# MAPE-CUN-Large-022.net
KiCad netlist of a schematic drawn in EAGLE
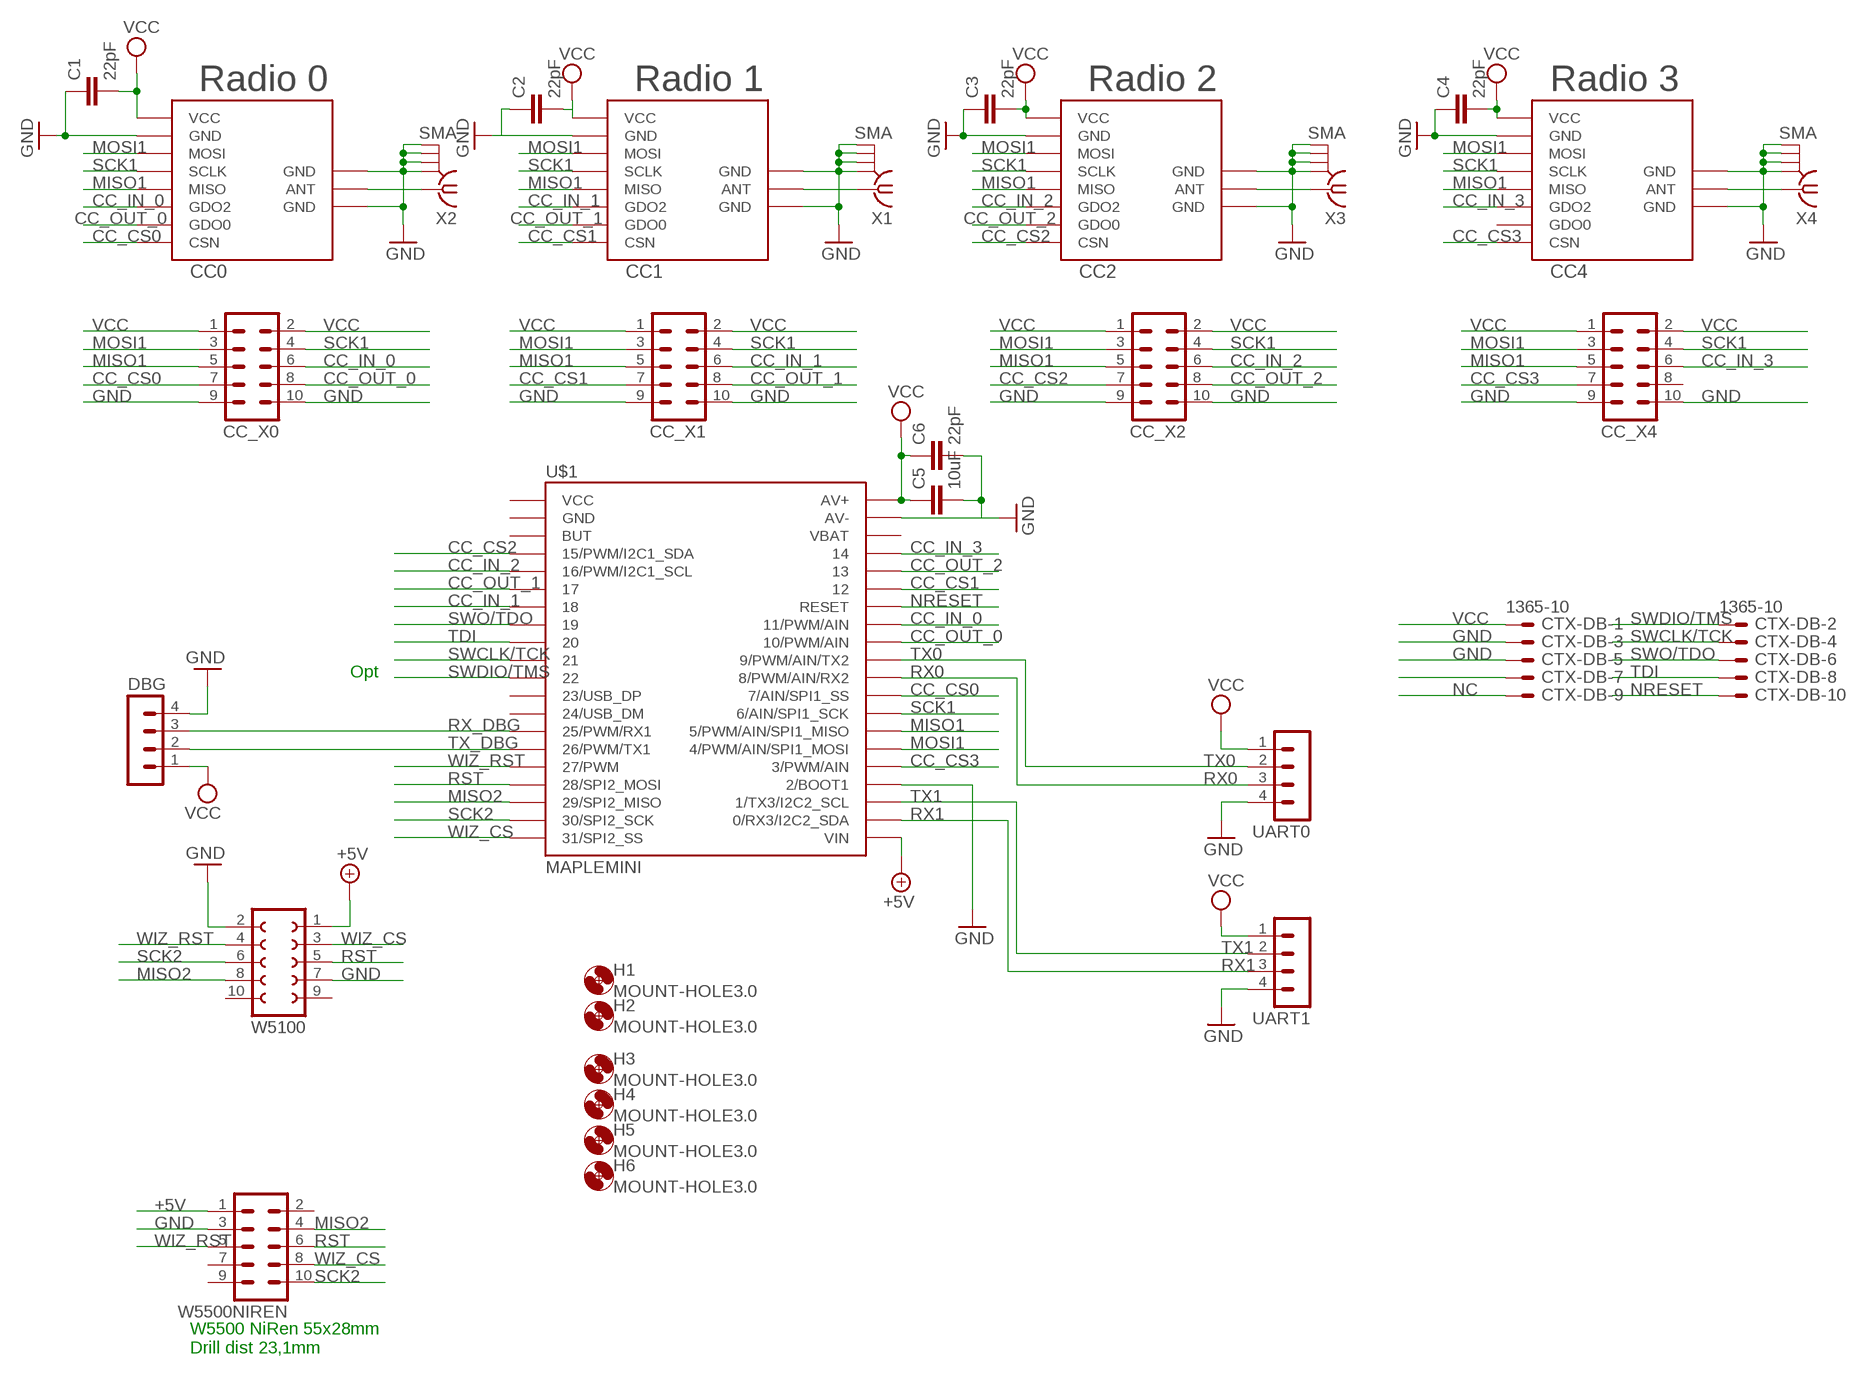
[diagram p0: schematic, sheet 1]

(export (version "E")
  (design (tool "Eeschema 10.0.6"))
  (components
    (comp (ref "C1")
      (value "22pF")
      (footprint "eagle-import:C0805")
      (libsource (lib "eagle-import") (part "C-EUC0805"))
    )
    (comp (ref "C2")
      (value "22pF")
      (footprint "eagle-import:C0805")
      (libsource (lib "eagle-import") (part "C-EUC0805"))
    )
    (comp (ref "C3")
      (value "22pF")
      (footprint "eagle-import:C0805")
      (libsource (lib "eagle-import") (part "C-EUC0805"))
    )
    (comp (ref "C4")
      (value "22pF")
      (footprint "eagle-import:C0805")
      (libsource (lib "eagle-import") (part "C-EUC0805"))
    )
    (comp (ref "C5")
      (value "10uF")
      (footprint "eagle-import:C1210")
      (libsource (lib "eagle-import") (part "C-EUC1210"))
    )
    (comp (ref "C6")
      (value "22pF")
      (footprint "eagle-import:C0805")
      (libsource (lib "eagle-import") (part "C-EUC0805"))
    )
    (comp (ref "CC0")
      (value "CC1101_MODULE1SMD")
      (footprint "eagle-import:CC1101_MODULE1_SMD")
      (libsource (lib "eagle-import") (part "CC1101_MODULE1SMD"))
    )
    (comp (ref "CC1")
      (value "CC1101_MODULE1SMD")
      (footprint "eagle-import:CC1101_MODULE1_SMD")
      (libsource (lib "eagle-import") (part "CC1101_MODULE1SMD"))
    )
    (comp (ref "CC2")
      (value "CC1101_MODULE1SMD")
      (footprint "eagle-import:CC1101_MODULE1_SMD")
      (libsource (lib "eagle-import") (part "CC1101_MODULE1SMD"))
    )
    (comp (ref "CC4")
      (value "CC1101_MODULE1SMD")
      (footprint "eagle-import:CC1101_MODULE1_SMD")
      (libsource (lib "eagle-import") (part "CC1101_MODULE1SMD"))
    )
    (comp (ref "CC_X0")
      (value "MA05-2")
      (footprint "eagle-import:MA05-2")
      (libsource (lib "eagle-import") (part "MA05-2"))
    )
    (comp (ref "CC_X1")
      (value "MA05-2")
      (footprint "eagle-import:MA05-2")
      (libsource (lib "eagle-import") (part "MA05-2"))
    )
    (comp (ref "CC_X2")
      (value "MA05-2")
      (footprint "eagle-import:MA05-2")
      (libsource (lib "eagle-import") (part "MA05-2"))
    )
    (comp (ref "CC_X4")
      (value "MA05-2")
      (footprint "eagle-import:MA05-2")
      (libsource (lib "eagle-import") (part "MA05-2"))
    )
    (comp (ref "CTX-DB")
      (value "1365-10")
      (footprint "eagle-import:1365-10")
      (libsource (lib "eagle-import") (part "1365-10"))
    )
    (comp (ref "DBG")
      (value "MA04-1")
      (footprint "eagle-import:MA04-1")
      (libsource (lib "eagle-import") (part "MA04-1"))
    )
    (comp (ref "H1")
      (value "MOUNT-HOLE3.0")
      (footprint "eagle-import:3,0")
      (libsource (lib "eagle-import") (part "MOUNT-HOLE3.0"))
    )
    (comp (ref "H2")
      (value "MOUNT-HOLE3.0")
      (footprint "eagle-import:3,0")
      (libsource (lib "eagle-import") (part "MOUNT-HOLE3.0"))
    )
    (comp (ref "H3")
      (value "MOUNT-HOLE3.0")
      (footprint "eagle-import:3,0")
      (libsource (lib "eagle-import") (part "MOUNT-HOLE3.0"))
    )
    (comp (ref "H4")
      (value "MOUNT-HOLE3.0")
      (footprint "eagle-import:3,0")
      (libsource (lib "eagle-import") (part "MOUNT-HOLE3.0"))
    )
    (comp (ref "H5")
      (value "MOUNT-HOLE3.0")
      (footprint "eagle-import:3,0")
      (libsource (lib "eagle-import") (part "MOUNT-HOLE3.0"))
    )
    (comp (ref "H6")
      (value "MOUNT-HOLE3.0")
      (footprint "eagle-import:3,0")
      (libsource (lib "eagle-import") (part "MOUNT-HOLE3.0"))
    )
    (comp (ref "U$1")
      (value "MAPLEMINI")
      (footprint "eagle-import:20-DIP")
      (libsource (lib "eagle-import") (part "MAPLEMINI"))
    )
    (comp (ref "UART0")
      (value "MA04-1")
      (footprint "eagle-import:MA04-1")
      (libsource (lib "eagle-import") (part "MA04-1"))
    )
    (comp (ref "UART1")
      (value "MA04-1")
      (footprint "eagle-import:MA04-1")
      (libsource (lib "eagle-import") (part "MA04-1"))
    )
    (comp (ref "W5100")
      (value "FE05-2")
      (footprint "eagle-import:FE05-2")
      (libsource (lib "eagle-import") (part "FE05-2"))
    )
    (comp (ref "W5500NIREN")
      (value "MA05-2")
      (footprint "eagle-import:MA05-2")
      (libsource (lib "eagle-import") (part "MA05-2"))
    )
    (comp (ref "X1")
      (value "SMA")
      (footprint "eagle-import:SMA")
      (libsource (lib "eagle-import") (part "SMA"))
    )
    (comp (ref "X2")
      (value "SMA")
      (footprint "eagle-import:SMA")
      (libsource (lib "eagle-import") (part "SMA"))
    )
    (comp (ref "X3")
      (value "SMA")
      (footprint "eagle-import:SMA")
      (libsource (lib "eagle-import") (part "SMA"))
    )
    (comp (ref "X4")
      (value "SMA")
      (footprint "eagle-import:SMA")
      (libsource (lib "eagle-import") (part "SMA"))
    )
  )
  (nets
    (net (code "1") (name "+5V") (class "Default")
      (node (ref "U$1") (pin "21") (pinfunction "VIN_21") (pintype "bidirectional"))
      (node (ref "W5100") (pin "1") (pinfunction "1_1") (pintype "passive"))
      (node (ref "W5500NIREN") (pin "1") (pinfunction "1_1") (pintype "passive"))
    )
    (net (code "2") (name "/CC_CS0") (class "Default")
      (node (ref "CC0") (pin "CSN") (pinfunction "CSN_CSN") (pintype "bidirectional"))
      (node (ref "CC_X0") (pin "7") (pinfunction "7_7") (pintype "passive"))
      (node (ref "U$1") (pin "29") (pinfunction "7/AIN/SPI1_SS_29") (pintype "bidirectional"))
    )
    (net (code "3") (name "/CC_CS1") (class "Default")
      (node (ref "CC1") (pin "CSN") (pinfunction "CSN_CSN") (pintype "bidirectional"))
      (node (ref "CC_X1") (pin "7") (pinfunction "7_7") (pintype "passive"))
      (node (ref "U$1") (pin "35") (pinfunction "12_35") (pintype "bidirectional"))
    )
    (net (code "4") (name "/CC_CS2") (class "Default")
      (node (ref "CC2") (pin "CSN") (pinfunction "CSN_CSN") (pintype "bidirectional"))
      (node (ref "CC_X2") (pin "7") (pinfunction "7_7") (pintype "passive"))
      (node (ref "U$1") (pin "4") (pinfunction "15/PWM/I2C1_SDA_4") (pintype "bidirectional"))
    )
    (net (code "5") (name "/CC_CS3") (class "Default")
      (node (ref "CC4") (pin "CSN") (pinfunction "CSN_CSN") (pintype "bidirectional"))
      (node (ref "CC_X4") (pin "7") (pinfunction "7_7") (pintype "passive"))
      (node (ref "U$1") (pin "25") (pinfunction "3/PWM/AIN_25") (pintype "bidirectional"))
    )
    (net (code "6") (name "/CC_IN_0") (class "Default")
      (node (ref "CC0") (pin "GDO2") (pinfunction "GDO2_GDO2") (pintype "bidirectional"))
      (node (ref "CC_X0") (pin "6") (pinfunction "6_6") (pintype "passive"))
      (node (ref "U$1") (pin "33") (pinfunction "11/PWM/AIN_33") (pintype "bidirectional"))
    )
    (net (code "7") (name "/CC_IN_1") (class "Default")
      (node (ref "CC1") (pin "GDO2") (pinfunction "GDO2_GDO2") (pintype "bidirectional"))
      (node (ref "CC_X1") (pin "6") (pinfunction "6_6") (pintype "passive"))
      (node (ref "U$1") (pin "7") (pinfunction "18_7") (pintype "bidirectional"))
    )
    (net (code "8") (name "/CC_IN_2") (class "Default")
      (node (ref "CC2") (pin "GDO2") (pinfunction "GDO2_GDO2") (pintype "bidirectional"))
      (node (ref "CC_X2") (pin "6") (pinfunction "6_6") (pintype "passive"))
      (node (ref "U$1") (pin "5") (pinfunction "16/PWM/I2C1_SCL_5") (pintype "bidirectional"))
    )
    (net (code "9") (name "/CC_IN_3") (class "Default")
      (node (ref "CC4") (pin "GDO2") (pinfunction "GDO2_GDO2") (pintype "bidirectional"))
      (node (ref "CC_X4") (pin "6") (pinfunction "6_6") (pintype "passive"))
      (node (ref "U$1") (pin "37") (pinfunction "14_37") (pintype "bidirectional"))
    )
    (net (code "10") (name "/CC_OUT_0") (class "Default")
      (node (ref "CC0") (pin "GDO0") (pinfunction "GDO0_GDO0") (pintype "bidirectional"))
      (node (ref "CC_X0") (pin "8") (pinfunction "8_8") (pintype "passive"))
      (node (ref "U$1") (pin "32") (pinfunction "10/PWM/AIN_32") (pintype "bidirectional"))
    )
    (net (code "11") (name "/CC_OUT_1") (class "Default")
      (node (ref "CC1") (pin "GDO0") (pinfunction "GDO0_GDO0") (pintype "bidirectional"))
      (node (ref "CC_X1") (pin "8") (pinfunction "8_8") (pintype "passive"))
      (node (ref "U$1") (pin "6") (pinfunction "17_6") (pintype "bidirectional"))
    )
    (net (code "12") (name "/CC_OUT_2") (class "Default")
      (node (ref "CC2") (pin "GDO0") (pinfunction "GDO0_GDO0") (pintype "bidirectional"))
      (node (ref "CC_X2") (pin "8") (pinfunction "8_8") (pintype "passive"))
      (node (ref "U$1") (pin "36") (pinfunction "13_36") (pintype "bidirectional"))
    )
    (net (code "13") (name "/MISO1") (class "Default")
      (node (ref "CC0") (pin "MISO") (pinfunction "MISO_MISO") (pintype "bidirectional"))
      (node (ref "CC1") (pin "MISO") (pinfunction "MISO_MISO") (pintype "bidirectional"))
      (node (ref "CC2") (pin "MISO") (pinfunction "MISO_MISO") (pintype "bidirectional"))
      (node (ref "CC4") (pin "MISO") (pinfunction "MISO_MISO") (pintype "bidirectional"))
      (node (ref "CC_X0") (pin "5") (pinfunction "5_5") (pintype "passive"))
      (node (ref "CC_X1") (pin "5") (pinfunction "5_5") (pintype "passive"))
      (node (ref "CC_X2") (pin "5") (pinfunction "5_5") (pintype "passive"))
      (node (ref "CC_X4") (pin "5") (pinfunction "5_5") (pintype "passive"))
      (node (ref "U$1") (pin "27") (pinfunction "5/PWM/AIN/SPI1_MISO_27") (pintype "bidirectional"))
    )
    (net (code "14") (name "/MISO2") (class "Default")
      (node (ref "U$1") (pin "18") (pinfunction "29/SPI2_MISO_18") (pintype "bidirectional"))
      (node (ref "W5100") (pin "8") (pinfunction "8_8") (pintype "passive"))
      (node (ref "W5500NIREN") (pin "4") (pinfunction "4_4") (pintype "passive"))
    )
    (net (code "15") (name "/MOSI1") (class "Default")
      (node (ref "CC0") (pin "MOSI") (pinfunction "MOSI_MOSI") (pintype "bidirectional"))
      (node (ref "CC1") (pin "MOSI") (pinfunction "MOSI_MOSI") (pintype "bidirectional"))
      (node (ref "CC2") (pin "MOSI") (pinfunction "MOSI_MOSI") (pintype "bidirectional"))
      (node (ref "CC4") (pin "MOSI") (pinfunction "MOSI_MOSI") (pintype "bidirectional"))
      (node (ref "CC_X0") (pin "3") (pinfunction "3_3") (pintype "passive"))
      (node (ref "CC_X1") (pin "3") (pinfunction "3_3") (pintype "passive"))
      (node (ref "CC_X2") (pin "3") (pinfunction "3_3") (pintype "passive"))
      (node (ref "CC_X4") (pin "3") (pinfunction "3_3") (pintype "passive"))
      (node (ref "U$1") (pin "26") (pinfunction "4/PWM/AIN/SPI1_MOSI_26") (pintype "bidirectional"))
    )
    (net (code "16") (name "/NC") (class "Default")
      (node (ref "CTX-DB") (pin "9") (pinfunction "S_9") (pintype "passive"))
    )
    (net (code "17") (name "/NRESET") (class "Default")
      (node (ref "CTX-DB") (pin "10") (pinfunction "S_10") (pintype "passive"))
      (node (ref "U$1") (pin "34") (pinfunction "RESET_34") (pintype "bidirectional"))
    )
    (net (code "18") (name "/RST") (class "Default")
      (node (ref "U$1") (pin "17") (pinfunction "28/SPI2_MOSI_17") (pintype "bidirectional"))
      (node (ref "W5100") (pin "5") (pinfunction "5_5") (pintype "passive"))
      (node (ref "W5500NIREN") (pin "6") (pinfunction "6_6") (pintype "passive"))
    )
    (net (code "19") (name "/RX0") (class "Default")
      (node (ref "U$1") (pin "30") (pinfunction "8/PWM/AIN/RX2_30") (pintype "bidirectional"))
      (node (ref "UART0") (pin "3") (pinfunction "3_3") (pintype "passive"))
    )
    (net (code "20") (name "/RX1") (class "Default")
      (node (ref "U$1") (pin "22") (pinfunction "0/RX3/I2C2_SDA_22") (pintype "bidirectional"))
      (node (ref "UART1") (pin "3") (pinfunction "3_3") (pintype "passive"))
    )
    (net (code "21") (name "/RX_DBG") (class "Default")
      (node (ref "DBG") (pin "3") (pinfunction "3_3") (pintype "passive"))
      (node (ref "U$1") (pin "14") (pinfunction "25/PWM/RX1_14") (pintype "bidirectional"))
    )
    (net (code "22") (name "/SCK1") (class "Default")
      (node (ref "CC0") (pin "SCLK") (pinfunction "SCLK_SCLK") (pintype "bidirectional"))
      (node (ref "CC1") (pin "SCLK") (pinfunction "SCLK_SCLK") (pintype "bidirectional"))
      (node (ref "CC2") (pin "SCLK") (pinfunction "SCLK_SCLK") (pintype "bidirectional"))
      (node (ref "CC4") (pin "SCLK") (pinfunction "SCLK_SCLK") (pintype "bidirectional"))
      (node (ref "CC_X0") (pin "4") (pinfunction "4_4") (pintype "passive"))
      (node (ref "CC_X1") (pin "4") (pinfunction "4_4") (pintype "passive"))
      (node (ref "CC_X2") (pin "4") (pinfunction "4_4") (pintype "passive"))
      (node (ref "CC_X4") (pin "4") (pinfunction "4_4") (pintype "passive"))
      (node (ref "U$1") (pin "28") (pinfunction "6/AIN/SPI1_SCK_28") (pintype "bidirectional"))
    )
    (net (code "23") (name "/SCK2") (class "Default")
      (node (ref "U$1") (pin "19") (pinfunction "30/SPI2_SCK_19") (pintype "bidirectional"))
      (node (ref "W5100") (pin "6") (pinfunction "6_6") (pintype "passive"))
      (node (ref "W5500NIREN") (pin "10") (pinfunction "10_10") (pintype "passive"))
    )
    (net (code "24") (name "/SWCLK{slash}TCK") (class "Default")
      (node (ref "CTX-DB") (pin "4") (pinfunction "S_4") (pintype "passive"))
      (node (ref "U$1") (pin "10") (pinfunction "21_10") (pintype "bidirectional"))
    )
    (net (code "25") (name "/SWDIO{slash}TMS") (class "Default")
      (node (ref "CTX-DB") (pin "2") (pinfunction "S_2") (pintype "passive"))
      (node (ref "U$1") (pin "11") (pinfunction "22_11") (pintype "bidirectional"))
    )
    (net (code "26") (name "/SWO{slash}TDO") (class "Default")
      (node (ref "CTX-DB") (pin "6") (pinfunction "S_6") (pintype "passive"))
      (node (ref "U$1") (pin "8") (pinfunction "19_8") (pintype "bidirectional"))
    )
    (net (code "27") (name "/TDI") (class "Default")
      (node (ref "CTX-DB") (pin "8") (pinfunction "S_8") (pintype "passive"))
      (node (ref "U$1") (pin "9") (pinfunction "20_9") (pintype "bidirectional"))
    )
    (net (code "28") (name "/TX0") (class "Default")
      (node (ref "U$1") (pin "31") (pinfunction "9/PWM/AIN/TX2_31") (pintype "bidirectional"))
      (node (ref "UART0") (pin "2") (pinfunction "2_2") (pintype "passive"))
    )
    (net (code "29") (name "/TX1") (class "Default")
      (node (ref "U$1") (pin "23") (pinfunction "1/TX3/I2C2_SCL_23") (pintype "bidirectional"))
      (node (ref "UART1") (pin "2") (pinfunction "2_2") (pintype "passive"))
    )
    (net (code "30") (name "/TX_DBG") (class "Default")
      (node (ref "DBG") (pin "2") (pinfunction "2_2") (pintype "passive"))
      (node (ref "U$1") (pin "15") (pinfunction "26/PWM/TX1_15") (pintype "bidirectional"))
    )
    (net (code "31") (name "/WIZ_CS") (class "Default")
      (node (ref "U$1") (pin "20") (pinfunction "31/SPI2_SS_20") (pintype "bidirectional"))
      (node (ref "W5100") (pin "3") (pinfunction "3_3") (pintype "passive"))
      (node (ref "W5500NIREN") (pin "8") (pinfunction "8_8") (pintype "passive"))
    )
    (net (code "32") (name "/WIZ_RST") (class "Default")
      (node (ref "U$1") (pin "16") (pinfunction "27/PWM_16") (pintype "bidirectional"))
      (node (ref "W5100") (pin "4") (pinfunction "4_4") (pintype "passive"))
      (node (ref "W5500NIREN") (pin "5") (pinfunction "5_5") (pintype "passive"))
    )
    (net (code "33") (name "GND") (class "Default")
      (node (ref "C1") (pin "1") (pinfunction "1_1") (pintype "passive"))
      (node (ref "C2") (pin "1") (pinfunction "1_1") (pintype "passive"))
      (node (ref "C3") (pin "1") (pinfunction "1_1") (pintype "passive"))
      (node (ref "C4") (pin "1") (pinfunction "1_1") (pintype "passive"))
      (node (ref "C5") (pin "2") (pinfunction "2_2") (pintype "passive"))
      (node (ref "C6") (pin "2") (pinfunction "2_2") (pintype "passive"))
      (node (ref "CC0") (pin "GND@0") (pinfunction "GND_GND@0") (pintype "power_in"))
      (node (ref "CC0") (pin "GND@1") (pinfunction "GND_GND@1") (pintype "power_in"))
      (node (ref "CC0") (pin "GND@2") (pinfunction "GND_GND@2") (pintype "power_in"))
      (node (ref "CC1") (pin "GND@0") (pinfunction "GND_GND@0") (pintype "power_in"))
      (node (ref "CC1") (pin "GND@1") (pinfunction "GND_GND@1") (pintype "power_in"))
      (node (ref "CC1") (pin "GND@2") (pinfunction "GND_GND@2") (pintype "power_in"))
      (node (ref "CC2") (pin "GND@0") (pinfunction "GND_GND@0") (pintype "power_in"))
      (node (ref "CC2") (pin "GND@1") (pinfunction "GND_GND@1") (pintype "power_in"))
      (node (ref "CC2") (pin "GND@2") (pinfunction "GND_GND@2") (pintype "power_in"))
      (node (ref "CC4") (pin "GND@0") (pinfunction "GND_GND@0") (pintype "power_in"))
      (node (ref "CC4") (pin "GND@1") (pinfunction "GND_GND@1") (pintype "power_in"))
      (node (ref "CC4") (pin "GND@2") (pinfunction "GND_GND@2") (pintype "power_in"))
      (node (ref "CC_X0") (pin "10") (pinfunction "10_10") (pintype "passive"))
      (node (ref "CC_X0") (pin "9") (pinfunction "9_9") (pintype "passive"))
      (node (ref "CC_X1") (pin "10") (pinfunction "10_10") (pintype "passive"))
      (node (ref "CC_X1") (pin "9") (pinfunction "9_9") (pintype "passive"))
      (node (ref "CC_X2") (pin "10") (pinfunction "10_10") (pintype "passive"))
      (node (ref "CC_X2") (pin "9") (pinfunction "9_9") (pintype "passive"))
      (node (ref "CC_X4") (pin "10") (pinfunction "10_10") (pintype "passive"))
      (node (ref "CC_X4") (pin "9") (pinfunction "9_9") (pintype "passive"))
      (node (ref "CTX-DB") (pin "3") (pinfunction "S_3") (pintype "passive"))
      (node (ref "CTX-DB") (pin "5") (pinfunction "S_5") (pintype "passive"))
      (node (ref "DBG") (pin "4") (pinfunction "4_4") (pintype "passive"))
      (node (ref "U$1") (pin "24") (pinfunction "2/BOOT1_24") (pintype "bidirectional"))
      (node (ref "U$1") (pin "39") (pinfunction "AV-_39") (pintype "bidirectional"))
      (node (ref "UART0") (pin "4") (pinfunction "4_4") (pintype "passive"))
      (node (ref "UART1") (pin "4") (pinfunction "4_4") (pintype "passive"))
      (node (ref "W5100") (pin "2") (pinfunction "2_2") (pintype "passive"))
      (node (ref "W5100") (pin "7") (pinfunction "7_7") (pintype "passive"))
      (node (ref "W5500NIREN") (pin "3") (pinfunction "3_3") (pintype "passive"))
      (node (ref "X1") (pin "GND@1") (pinfunction "2_GND@1") (pintype "passive"))
      (node (ref "X1") (pin "GND@2") (pinfunction "3_GND@2") (pintype "passive"))
      (node (ref "X1") (pin "GND@3") (pinfunction "4_GND@3") (pintype "passive"))
      (node (ref "X1") (pin "GND@4") (pinfunction "5_GND@4") (pintype "passive"))
      (node (ref "X2") (pin "GND@1") (pinfunction "2_GND@1") (pintype "passive"))
      (node (ref "X2") (pin "GND@2") (pinfunction "3_GND@2") (pintype "passive"))
      (node (ref "X2") (pin "GND@3") (pinfunction "4_GND@3") (pintype "passive"))
      (node (ref "X2") (pin "GND@4") (pinfunction "5_GND@4") (pintype "passive"))
      (node (ref "X3") (pin "GND@1") (pinfunction "2_GND@1") (pintype "passive"))
      (node (ref "X3") (pin "GND@2") (pinfunction "3_GND@2") (pintype "passive"))
      (node (ref "X3") (pin "GND@3") (pinfunction "4_GND@3") (pintype "passive"))
      (node (ref "X3") (pin "GND@4") (pinfunction "5_GND@4") (pintype "passive"))
      (node (ref "X4") (pin "GND@1") (pinfunction "2_GND@1") (pintype "passive"))
      (node (ref "X4") (pin "GND@2") (pinfunction "3_GND@2") (pintype "passive"))
      (node (ref "X4") (pin "GND@3") (pinfunction "4_GND@3") (pintype "passive"))
      (node (ref "X4") (pin "GND@4") (pinfunction "5_GND@4") (pintype "passive"))
    )
    (net (code "34") (name "Net-(CC0-PadANT)") (class "Default")
      (node (ref "CC0") (pin "ANT") (pinfunction "ANT_ANT") (pintype "output"))
      (node (ref "X2") (pin "1") (pinfunction "1_1") (pintype "passive"))
    )
    (net (code "35") (name "Net-(CC1-PadANT)") (class "Default")
      (node (ref "CC1") (pin "ANT") (pinfunction "ANT_ANT") (pintype "output"))
      (node (ref "X1") (pin "1") (pinfunction "1_1") (pintype "passive"))
    )
    (net (code "36") (name "Net-(CC2-PadANT)") (class "Default")
      (node (ref "CC2") (pin "ANT") (pinfunction "ANT_ANT") (pintype "output"))
      (node (ref "X3") (pin "1") (pinfunction "1_1") (pintype "passive"))
    )
    (net (code "37") (name "Net-(CC4-PadANT)") (class "Default")
      (node (ref "CC4") (pin "ANT") (pinfunction "ANT_ANT") (pintype "output"))
      (node (ref "X4") (pin "1") (pinfunction "1_1") (pintype "passive"))
    )
    (net (code "38") (name "VCC") (class "Default")
      (node (ref "C1") (pin "2") (pinfunction "2_2") (pintype "passive"))
      (node (ref "C2") (pin "2") (pinfunction "2_2") (pintype "passive"))
      (node (ref "C3") (pin "2") (pinfunction "2_2") (pintype "passive"))
      (node (ref "C4") (pin "2") (pinfunction "2_2") (pintype "passive"))
      (node (ref "C5") (pin "1") (pinfunction "1_1") (pintype "passive"))
      (node (ref "C6") (pin "1") (pinfunction "1_1") (pintype "passive"))
      (node (ref "CC0") (pin "VCC") (pinfunction "VCC_VCC") (pintype "power_in"))
      (node (ref "CC1") (pin "VCC") (pinfunction "VCC_VCC") (pintype "power_in"))
      (node (ref "CC2") (pin "VCC") (pinfunction "VCC_VCC") (pintype "power_in"))
      (node (ref "CC4") (pin "VCC") (pinfunction "VCC_VCC") (pintype "power_in"))
      (node (ref "CC_X0") (pin "1") (pinfunction "1_1") (pintype "passive"))
      (node (ref "CC_X0") (pin "2") (pinfunction "2_2") (pintype "passive"))
      (node (ref "CC_X1") (pin "1") (pinfunction "1_1") (pintype "passive"))
      (node (ref "CC_X1") (pin "2") (pinfunction "2_2") (pintype "passive"))
      (node (ref "CC_X2") (pin "1") (pinfunction "1_1") (pintype "passive"))
      (node (ref "CC_X2") (pin "2") (pinfunction "2_2") (pintype "passive"))
      (node (ref "CC_X4") (pin "1") (pinfunction "1_1") (pintype "passive"))
      (node (ref "CC_X4") (pin "2") (pinfunction "2_2") (pintype "passive"))
      (node (ref "CTX-DB") (pin "1") (pinfunction "S_1") (pintype "passive"))
      (node (ref "DBG") (pin "1") (pinfunction "1_1") (pintype "passive"))
      (node (ref "U$1") (pin "40") (pinfunction "AV+_40") (pintype "bidirectional"))
      (node (ref "UART0") (pin "1") (pinfunction "1_1") (pintype "passive"))
      (node (ref "UART1") (pin "1") (pinfunction "1_1") (pintype "passive"))
    )
    (net (code "39") (name "unconnected-(CC4-PadGDO0)") (class "Default")
      (node (ref "CC4") (pin "GDO0") (pinfunction "GDO0_GDO0") (pintype "bidirectional"))
    )
    (net (code "40") (name "unconnected-(CC_X4-Pad8)") (class "Default")
      (node (ref "CC_X4") (pin "8") (pinfunction "8_8") (pintype "passive"))
    )
    (net (code "41") (name "unconnected-(CTX-DBH-S-Pad7)") (class "Default")
      (node (ref "CTX-DB") (pin "7") (pinfunction "S_7") (pintype "passive"))
    )
    (net (code "42") (name "unconnected-(U$1-23{slash}USB_DP-Pad12)") (class "Default")
      (node (ref "U$1") (pin "12") (pinfunction "23/USB_DP_12") (pintype "bidirectional"))
    )
    (net (code "43") (name "unconnected-(U$1-24{slash}USB_DM-Pad13)") (class "Default")
      (node (ref "U$1") (pin "13") (pinfunction "24/USB_DM_13") (pintype "bidirectional"))
    )
    (net (code "44") (name "unconnected-(U$1-BUT-Pad3)") (class "Default")
      (node (ref "U$1") (pin "3") (pinfunction "BUT_3") (pintype "bidirectional"))
    )
    (net (code "45") (name "unconnected-(U$1-GND-Pad2)") (class "Default")
      (node (ref "U$1") (pin "2") (pinfunction "GND_2") (pintype "bidirectional"))
    )
    (net (code "46") (name "unconnected-(U$1-VBAT-Pad38)") (class "Default")
      (node (ref "U$1") (pin "38") (pinfunction "VBAT_38") (pintype "bidirectional"))
    )
    (net (code "47") (name "unconnected-(U$1-VCC-Pad1)") (class "Default")
      (node (ref "U$1") (pin "1") (pinfunction "VCC_1") (pintype "bidirectional"))
    )
    (net (code "48") (name "unconnected-(W5100-Pad9)") (class "Default")
      (node (ref "W5100") (pin "9") (pinfunction "9_9") (pintype "passive"))
    )
    (net (code "49") (name "unconnected-(W5100-Pad10)") (class "Default")
      (node (ref "W5100") (pin "10") (pinfunction "10_10") (pintype "passive"))
    )
    (net (code "50") (name "unconnected-(W5500NIREN-Pad2)") (class "Default")
      (node (ref "W5500NIREN") (pin "2") (pinfunction "2_2") (pintype "passive"))
    )
    (net (code "51") (name "unconnected-(W5500NIREN-Pad7)") (class "Default")
      (node (ref "W5500NIREN") (pin "7") (pinfunction "7_7") (pintype "passive"))
    )
    (net (code "52") (name "unconnected-(W5500NIREN-Pad9)") (class "Default")
      (node (ref "W5500NIREN") (pin "9") (pinfunction "9_9") (pintype "passive"))
    )
  )
)
